# PiKVM_USB_Adapter_v1.net
KiCad netlist of a schematic drawn in EAGLE
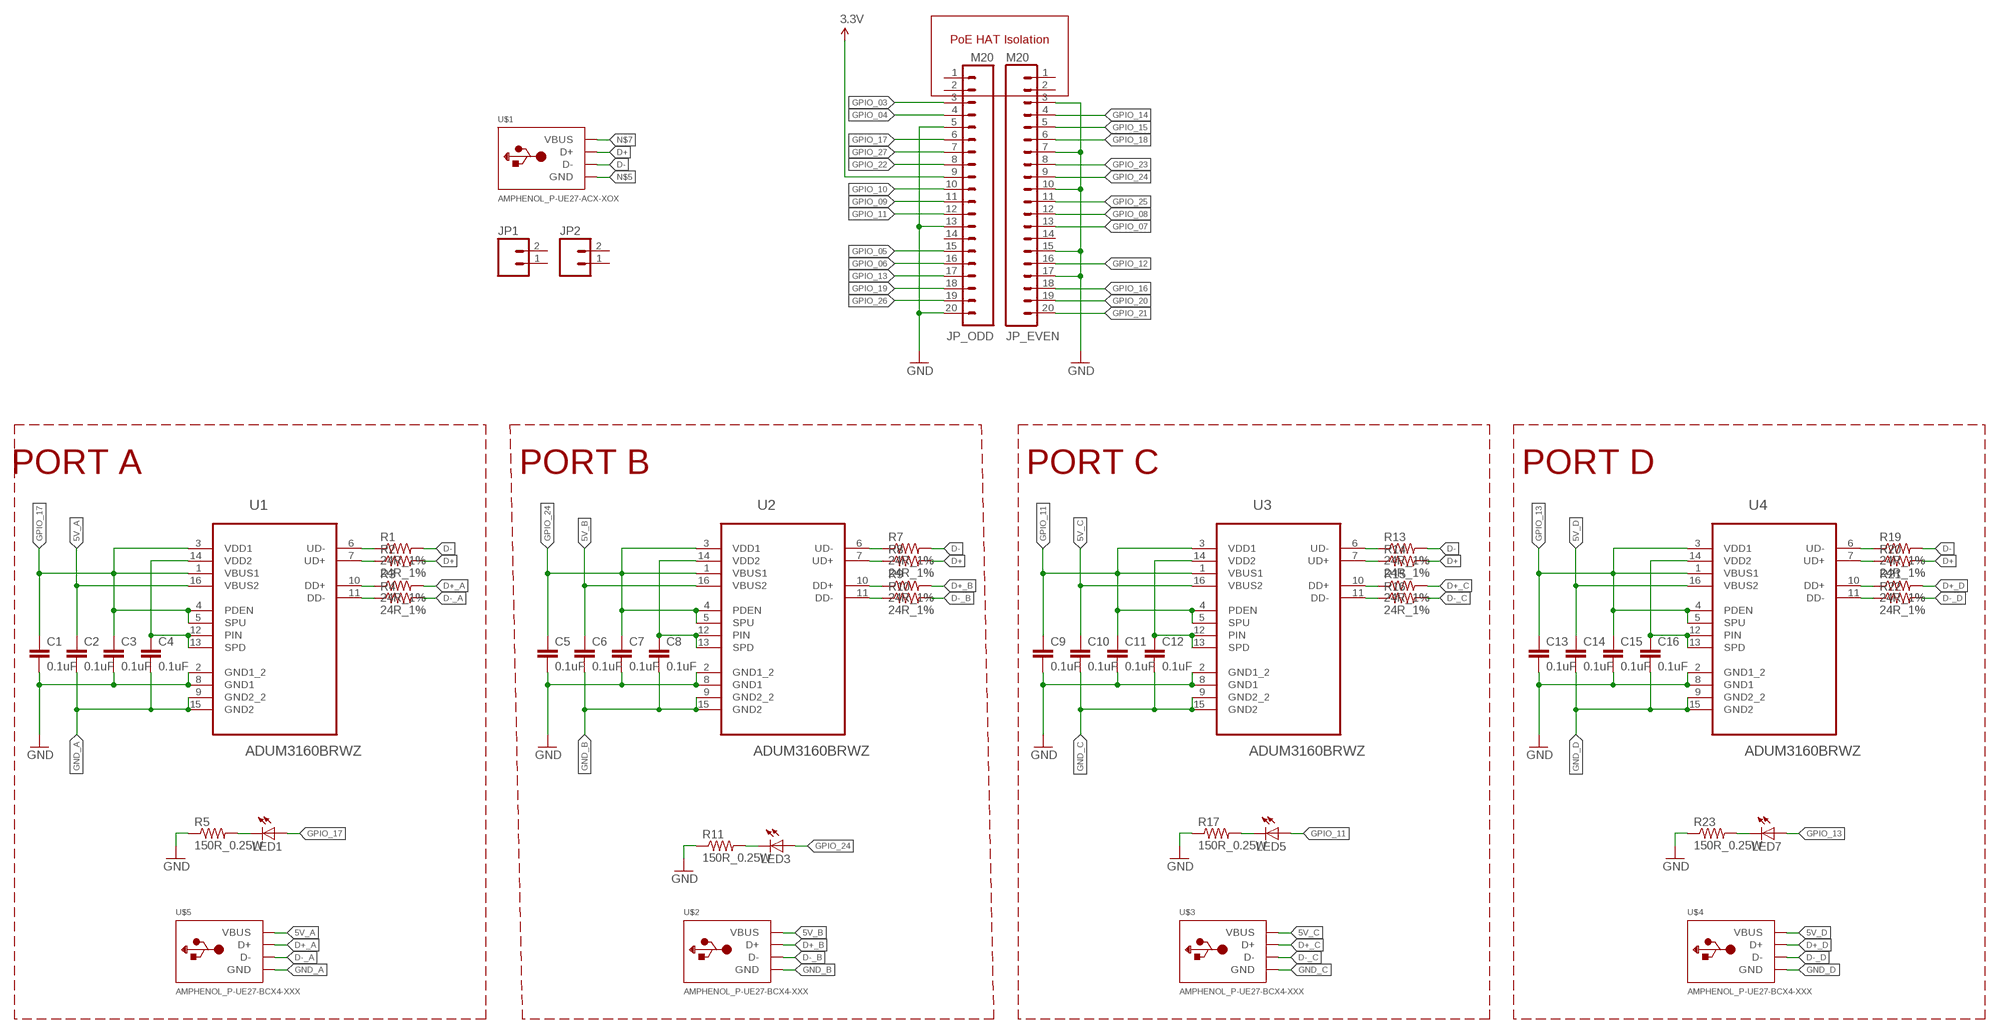
[diagram p0: schematic, sheet 1]

(export (version "E")
  (design (tool "Eeschema 10.0.6"))
  (components
    (comp (ref "C1")
      (value "0.1uF")
      (footprint "eagle-import:0805")
      (libsource (lib "eagle-import") (part "CAP0805"))
    )
    (comp (ref "C2")
      (value "0.1uF")
      (footprint "eagle-import:0805")
      (libsource (lib "eagle-import") (part "CAP0805"))
    )
    (comp (ref "C3")
      (value "0.1uF")
      (footprint "eagle-import:0805")
      (libsource (lib "eagle-import") (part "CAP0805"))
    )
    (comp (ref "C4")
      (value "0.1uF")
      (footprint "eagle-import:0805")
      (libsource (lib "eagle-import") (part "CAP0805"))
    )
    (comp (ref "C5")
      (value "0.1uF")
      (footprint "eagle-import:0805")
      (libsource (lib "eagle-import") (part "CAP0805"))
    )
    (comp (ref "C6")
      (value "0.1uF")
      (footprint "eagle-import:0805")
      (libsource (lib "eagle-import") (part "CAP0805"))
    )
    (comp (ref "C7")
      (value "0.1uF")
      (footprint "eagle-import:0805")
      (libsource (lib "eagle-import") (part "CAP0805"))
    )
    (comp (ref "C8")
      (value "0.1uF")
      (footprint "eagle-import:0805")
      (libsource (lib "eagle-import") (part "CAP0805"))
    )
    (comp (ref "C9")
      (value "0.1uF")
      (footprint "eagle-import:0805")
      (libsource (lib "eagle-import") (part "CAP0805"))
    )
    (comp (ref "C10")
      (value "0.1uF")
      (footprint "eagle-import:0805")
      (libsource (lib "eagle-import") (part "CAP0805"))
    )
    (comp (ref "C11")
      (value "0.1uF")
      (footprint "eagle-import:0805")
      (libsource (lib "eagle-import") (part "CAP0805"))
    )
    (comp (ref "C12")
      (value "0.1uF")
      (footprint "eagle-import:0805")
      (libsource (lib "eagle-import") (part "CAP0805"))
    )
    (comp (ref "C13")
      (value "0.1uF")
      (footprint "eagle-import:0805")
      (libsource (lib "eagle-import") (part "CAP0805"))
    )
    (comp (ref "C14")
      (value "0.1uF")
      (footprint "eagle-import:0805")
      (libsource (lib "eagle-import") (part "CAP0805"))
    )
    (comp (ref "C15")
      (value "0.1uF")
      (footprint "eagle-import:0805")
      (libsource (lib "eagle-import") (part "CAP0805"))
    )
    (comp (ref "C16")
      (value "0.1uF")
      (footprint "eagle-import:0805")
      (libsource (lib "eagle-import") (part "CAP0805"))
    )
    (comp (ref "JP1")
      (value "M02LOCK")
      (footprint "eagle-import:1X02_LOCK")
      (libsource (lib "eagle-import") (part "M02LOCK"))
    )
    (comp (ref "JP2")
      (value "M02LOCK")
      (footprint "eagle-import:1X02_LOCK")
      (libsource (lib "eagle-import") (part "M02LOCK"))
    )
    (comp (ref "JP_EVEN")
      (value "M20")
      (footprint "eagle-import:1X20")
      (libsource (lib "eagle-import") (part "M20"))
    )
    (comp (ref "JP_ODD")
      (value "M20")
      (footprint "eagle-import:1X20")
      (libsource (lib "eagle-import") (part "M20"))
    )
    (comp (ref "LED1")
      (value "LED1206")
      (footprint "eagle-import:LED-1206")
      (libsource (lib "eagle-import") (part "LED1206"))
    )
    (comp (ref "LED3")
      (value "LED1206")
      (footprint "eagle-import:LED-1206")
      (libsource (lib "eagle-import") (part "LED1206"))
    )
    (comp (ref "LED5")
      (value "LED1206")
      (footprint "eagle-import:LED-1206")
      (libsource (lib "eagle-import") (part "LED1206"))
    )
    (comp (ref "LED7")
      (value "LED1206")
      (footprint "eagle-import:LED-1206")
      (libsource (lib "eagle-import") (part "LED1206"))
    )
    (comp (ref "R1")
      (value "24R_1%")
      (footprint "eagle-import:0805")
      (libsource (lib "eagle-import") (part "RESISTOR0805-RES"))
    )
    (comp (ref "R2")
      (value "24R_1%")
      (footprint "eagle-import:0805")
      (libsource (lib "eagle-import") (part "RESISTOR0805-RES"))
    )
    (comp (ref "R3")
      (value "24R_1%")
      (footprint "eagle-import:0805")
      (libsource (lib "eagle-import") (part "RESISTOR0805-RES"))
    )
    (comp (ref "R4")
      (value "24R_1%")
      (footprint "eagle-import:0805")
      (libsource (lib "eagle-import") (part "RESISTOR0805-RES"))
    )
    (comp (ref "R5")
      (value "150R_0.25W")
      (footprint "eagle-import:1206")
      (libsource (lib "eagle-import") (part "RESISTOR1206"))
    )
    (comp (ref "R7")
      (value "24R_1%")
      (footprint "eagle-import:0805")
      (libsource (lib "eagle-import") (part "RESISTOR0805-RES"))
    )
    (comp (ref "R8")
      (value "24R_1%")
      (footprint "eagle-import:0805")
      (libsource (lib "eagle-import") (part "RESISTOR0805-RES"))
    )
    (comp (ref "R9")
      (value "24R_1%")
      (footprint "eagle-import:0805")
      (libsource (lib "eagle-import") (part "RESISTOR0805-RES"))
    )
    (comp (ref "R10")
      (value "24R_1%")
      (footprint "eagle-import:0805")
      (libsource (lib "eagle-import") (part "RESISTOR0805-RES"))
    )
    (comp (ref "R11")
      (value "150R_0.25W")
      (footprint "eagle-import:1206")
      (libsource (lib "eagle-import") (part "RESISTOR1206"))
    )
    (comp (ref "R13")
      (value "24R_1%")
      (footprint "eagle-import:0805")
      (libsource (lib "eagle-import") (part "RESISTOR0805-RES"))
    )
    (comp (ref "R14")
      (value "24R_1%")
      (footprint "eagle-import:0805")
      (libsource (lib "eagle-import") (part "RESISTOR0805-RES"))
    )
    (comp (ref "R15")
      (value "24R_1%")
      (footprint "eagle-import:0805")
      (libsource (lib "eagle-import") (part "RESISTOR0805-RES"))
    )
    (comp (ref "R16")
      (value "24R_1%")
      (footprint "eagle-import:0805")
      (libsource (lib "eagle-import") (part "RESISTOR0805-RES"))
    )
    (comp (ref "R17")
      (value "150R_0.25W")
      (footprint "eagle-import:1206")
      (libsource (lib "eagle-import") (part "RESISTOR1206"))
    )
    (comp (ref "R19")
      (value "24R_1%")
      (footprint "eagle-import:0805")
      (libsource (lib "eagle-import") (part "RESISTOR0805-RES"))
    )
    (comp (ref "R20")
      (value "24R_1%")
      (footprint "eagle-import:0805")
      (libsource (lib "eagle-import") (part "RESISTOR0805-RES"))
    )
    (comp (ref "R21")
      (value "24R_1%")
      (footprint "eagle-import:0805")
      (libsource (lib "eagle-import") (part "RESISTOR0805-RES"))
    )
    (comp (ref "R22")
      (value "24R_1%")
      (footprint "eagle-import:0805")
      (libsource (lib "eagle-import") (part "RESISTOR0805-RES"))
    )
    (comp (ref "R23")
      (value "150R_0.25W")
      (footprint "eagle-import:1206")
      (libsource (lib "eagle-import") (part "RESISTOR1206"))
    )
    (comp (ref "U$1")
      (value "AMPHENOL_P-UE27-ACX-XOX")
      (footprint "eagle-import:USBA_AMPHENOL-UE27-RA")
      (libsource (lib "eagle-import") (part "AMPHENOL_P-UE27-ACX-XOX"))
    )
    (comp (ref "U$2")
      (value "AMPHENOL_P-UE27-BCX4-XXX")
      (footprint "eagle-import:USBB_AMPHENOL-UE27-BC")
      (libsource (lib "eagle-import") (part "AMPHENOL_P-UE27-BCX4-XXX"))
    )
    (comp (ref "U$3")
      (value "AMPHENOL_P-UE27-BCX4-XXX")
      (footprint "eagle-import:USBB_AMPHENOL-UE27-BC")
      (libsource (lib "eagle-import") (part "AMPHENOL_P-UE27-BCX4-XXX"))
    )
    (comp (ref "U$4")
      (value "AMPHENOL_P-UE27-BCX4-XXX")
      (footprint "eagle-import:USBB_AMPHENOL-UE27-BC")
      (libsource (lib "eagle-import") (part "AMPHENOL_P-UE27-BCX4-XXX"))
    )
    (comp (ref "U$5")
      (value "AMPHENOL_P-UE27-BCX4-XXX")
      (footprint "eagle-import:USBB_AMPHENOL-UE27-BC")
      (libsource (lib "eagle-import") (part "AMPHENOL_P-UE27-BCX4-XXX"))
    )
    (comp (ref "U1")
      (value "ADUM3160BRWZ")
      (footprint "eagle-import:SOIC127P1032X265-16N")
      (libsource (lib "eagle-import") (part "ADUM3160BRWZ"))
    )
    (comp (ref "U2")
      (value "ADUM3160BRWZ")
      (footprint "eagle-import:SOIC127P1032X265-16N")
      (libsource (lib "eagle-import") (part "ADUM3160BRWZ"))
    )
    (comp (ref "U3")
      (value "ADUM3160BRWZ")
      (footprint "eagle-import:SOIC127P1032X265-16N")
      (libsource (lib "eagle-import") (part "ADUM3160BRWZ"))
    )
    (comp (ref "U4")
      (value "ADUM3160BRWZ")
      (footprint "eagle-import:SOIC127P1032X265-16N")
      (libsource (lib "eagle-import") (part "ADUM3160BRWZ"))
    )
  )
  (nets
    (net (code "1") (name "3.3V") (class "Default")
      (node (ref "JP_ODD") (pin "9") (pinfunction "9_9") (pintype "passive"))
    )
    (net (code "2") (name "5V_A") (class "Default")
      (node (ref "C2") (pin "1") (pinfunction "1_1") (pintype "passive"))
      (node (ref "U$5") (pin "P$1") (pinfunction "VBUS_P$1") (pintype "power_in"))
      (node (ref "U1") (pin "16") (pinfunction "VBUS2_16") (pintype "power_in"))
    )
    (net (code "3") (name "5V_B") (class "Default")
      (node (ref "C6") (pin "1") (pinfunction "1_1") (pintype "passive"))
      (node (ref "U$2") (pin "P$1") (pinfunction "VBUS_P$1") (pintype "power_in"))
      (node (ref "U2") (pin "16") (pinfunction "VBUS2_16") (pintype "power_in"))
    )
    (net (code "4") (name "5V_C") (class "Default")
      (node (ref "C10") (pin "1") (pinfunction "1_1") (pintype "passive"))
      (node (ref "U$3") (pin "P$1") (pinfunction "VBUS_P$1") (pintype "power_in"))
      (node (ref "U3") (pin "16") (pinfunction "VBUS2_16") (pintype "power_in"))
    )
    (net (code "5") (name "5V_D") (class "Default")
      (node (ref "C14") (pin "1") (pinfunction "1_1") (pintype "passive"))
      (node (ref "U$4") (pin "P$1") (pinfunction "VBUS_P$1") (pintype "power_in"))
      (node (ref "U4") (pin "16") (pinfunction "VBUS2_16") (pintype "power_in"))
    )
    (net (code "6") (name "D+") (class "Default")
      (node (ref "R14") (pin "2") (pinfunction "2_2") (pintype "passive"))
      (node (ref "R2") (pin "2") (pinfunction "2_2") (pintype "passive"))
      (node (ref "R20") (pin "2") (pinfunction "2_2") (pintype "passive"))
      (node (ref "R8") (pin "2") (pinfunction "2_2") (pintype "passive"))
      (node (ref "U$1") (pin "P$3") (pinfunction "D+_P$3") (pintype "bidirectional"))
    )
    (net (code "7") (name "D+_A") (class "Default")
      (node (ref "R3") (pin "2") (pinfunction "2_2") (pintype "passive"))
      (node (ref "U$5") (pin "P$3") (pinfunction "D+_P$3") (pintype "bidirectional"))
    )
    (net (code "8") (name "D+_B") (class "Default")
      (node (ref "R9") (pin "2") (pinfunction "2_2") (pintype "passive"))
      (node (ref "U$2") (pin "P$3") (pinfunction "D+_P$3") (pintype "bidirectional"))
    )
    (net (code "9") (name "D+_C") (class "Default")
      (node (ref "R15") (pin "2") (pinfunction "2_2") (pintype "passive"))
      (node (ref "U$3") (pin "P$3") (pinfunction "D+_P$3") (pintype "bidirectional"))
    )
    (net (code "10") (name "D+_D") (class "Default")
      (node (ref "R21") (pin "2") (pinfunction "2_2") (pintype "passive"))
      (node (ref "U$4") (pin "P$3") (pinfunction "D+_P$3") (pintype "bidirectional"))
    )
    (net (code "11") (name "D-") (class "Default")
      (node (ref "R1") (pin "2") (pinfunction "2_2") (pintype "passive"))
      (node (ref "R13") (pin "2") (pinfunction "2_2") (pintype "passive"))
      (node (ref "R19") (pin "2") (pinfunction "2_2") (pintype "passive"))
      (node (ref "R7") (pin "2") (pinfunction "2_2") (pintype "passive"))
      (node (ref "U$1") (pin "P$2") (pinfunction "D-_P$2") (pintype "bidirectional"))
    )
    (net (code "12") (name "D-_A") (class "Default")
      (node (ref "R4") (pin "2") (pinfunction "2_2") (pintype "passive"))
      (node (ref "U$5") (pin "P$2") (pinfunction "D-_P$2") (pintype "bidirectional"))
    )
    (net (code "13") (name "D-_B") (class "Default")
      (node (ref "R10") (pin "2") (pinfunction "2_2") (pintype "passive"))
      (node (ref "U$2") (pin "P$2") (pinfunction "D-_P$2") (pintype "bidirectional"))
    )
    (net (code "14") (name "D-_C") (class "Default")
      (node (ref "R16") (pin "2") (pinfunction "2_2") (pintype "passive"))
      (node (ref "U$3") (pin "P$2") (pinfunction "D-_P$2") (pintype "bidirectional"))
    )
    (net (code "15") (name "D-_D") (class "Default")
      (node (ref "R22") (pin "2") (pinfunction "2_2") (pintype "passive"))
      (node (ref "U$4") (pin "P$2") (pinfunction "D-_P$2") (pintype "bidirectional"))
    )
    (net (code "16") (name "GND") (class "Default")
      (node (ref "C1") (pin "2") (pinfunction "2_2") (pintype "passive"))
      (node (ref "C11") (pin "2") (pinfunction "2_2") (pintype "passive"))
      (node (ref "C13") (pin "2") (pinfunction "2_2") (pintype "passive"))
      (node (ref "C15") (pin "2") (pinfunction "2_2") (pintype "passive"))
      (node (ref "C3") (pin "2") (pinfunction "2_2") (pintype "passive"))
      (node (ref "C5") (pin "2") (pinfunction "2_2") (pintype "passive"))
      (node (ref "C7") (pin "2") (pinfunction "2_2") (pintype "passive"))
      (node (ref "C9") (pin "2") (pinfunction "2_2") (pintype "passive"))
      (node (ref "JP_EVEN") (pin "10") (pinfunction "10_10") (pintype "passive"))
      (node (ref "JP_EVEN") (pin "15") (pinfunction "15_15") (pintype "passive"))
      (node (ref "JP_EVEN") (pin "17") (pinfunction "17_17") (pintype "passive"))
      (node (ref "JP_EVEN") (pin "3") (pinfunction "3_3") (pintype "passive"))
      (node (ref "JP_EVEN") (pin "7") (pinfunction "7_7") (pintype "passive"))
      (node (ref "JP_ODD") (pin "13") (pinfunction "13_13") (pintype "passive"))
      (node (ref "JP_ODD") (pin "20") (pinfunction "20_20") (pintype "passive"))
      (node (ref "JP_ODD") (pin "5") (pinfunction "5_5") (pintype "passive"))
      (node (ref "R11") (pin "1") (pinfunction "1_1") (pintype "passive"))
      (node (ref "R17") (pin "1") (pinfunction "1_1") (pintype "passive"))
      (node (ref "R23") (pin "1") (pinfunction "1_1") (pintype "passive"))
      (node (ref "R5") (pin "1") (pinfunction "1_1") (pintype "passive"))
      (node (ref "U1") (pin "2") (pinfunction "GND1_2_2") (pintype "passive"))
      (node (ref "U1") (pin "8") (pinfunction "GND1_8") (pintype "passive"))
      (node (ref "U2") (pin "2") (pinfunction "GND1_2_2") (pintype "passive"))
      (node (ref "U2") (pin "8") (pinfunction "GND1_8") (pintype "passive"))
      (node (ref "U3") (pin "2") (pinfunction "GND1_2_2") (pintype "passive"))
      (node (ref "U3") (pin "8") (pinfunction "GND1_8") (pintype "passive"))
      (node (ref "U4") (pin "2") (pinfunction "GND1_2_2") (pintype "passive"))
      (node (ref "U4") (pin "8") (pinfunction "GND1_8") (pintype "passive"))
    )
    (net (code "17") (name "GND_A") (class "Default")
      (node (ref "C2") (pin "2") (pinfunction "2_2") (pintype "passive"))
      (node (ref "C4") (pin "2") (pinfunction "2_2") (pintype "passive"))
      (node (ref "U$5") (pin "P$4") (pinfunction "GND_P$4") (pintype "power_in"))
      (node (ref "U1") (pin "15") (pinfunction "GND2_15") (pintype "passive"))
      (node (ref "U1") (pin "9") (pinfunction "GND2_2_9") (pintype "passive"))
    )
    (net (code "18") (name "GND_B") (class "Default")
      (node (ref "C6") (pin "2") (pinfunction "2_2") (pintype "passive"))
      (node (ref "C8") (pin "2") (pinfunction "2_2") (pintype "passive"))
      (node (ref "U$2") (pin "P$4") (pinfunction "GND_P$4") (pintype "power_in"))
      (node (ref "U2") (pin "15") (pinfunction "GND2_15") (pintype "passive"))
      (node (ref "U2") (pin "9") (pinfunction "GND2_2_9") (pintype "passive"))
    )
    (net (code "19") (name "GND_C") (class "Default")
      (node (ref "C10") (pin "2") (pinfunction "2_2") (pintype "passive"))
      (node (ref "C12") (pin "2") (pinfunction "2_2") (pintype "passive"))
      (node (ref "U$3") (pin "P$4") (pinfunction "GND_P$4") (pintype "power_in"))
      (node (ref "U3") (pin "15") (pinfunction "GND2_15") (pintype "passive"))
      (node (ref "U3") (pin "9") (pinfunction "GND2_2_9") (pintype "passive"))
    )
    (net (code "20") (name "GND_D") (class "Default")
      (node (ref "C14") (pin "2") (pinfunction "2_2") (pintype "passive"))
      (node (ref "C16") (pin "2") (pinfunction "2_2") (pintype "passive"))
      (node (ref "U$4") (pin "P$4") (pinfunction "GND_P$4") (pintype "power_in"))
      (node (ref "U4") (pin "15") (pinfunction "GND2_15") (pintype "passive"))
      (node (ref "U4") (pin "9") (pinfunction "GND2_2_9") (pintype "passive"))
    )
    (net (code "21") (name "GPIO_03") (class "Default")
      (node (ref "JP_ODD") (pin "3") (pinfunction "3_3") (pintype "passive"))
    )
    (net (code "22") (name "GPIO_04") (class "Default")
      (node (ref "JP_ODD") (pin "4") (pinfunction "4_4") (pintype "passive"))
    )
    (net (code "23") (name "GPIO_05") (class "Default")
      (node (ref "JP_ODD") (pin "15") (pinfunction "15_15") (pintype "passive"))
    )
    (net (code "24") (name "GPIO_06") (class "Default")
      (node (ref "JP_ODD") (pin "16") (pinfunction "16_16") (pintype "passive"))
    )
    (net (code "25") (name "GPIO_07") (class "Default")
      (node (ref "JP_EVEN") (pin "13") (pinfunction "13_13") (pintype "passive"))
    )
    (net (code "26") (name "GPIO_08") (class "Default")
      (node (ref "JP_EVEN") (pin "12") (pinfunction "12_12") (pintype "passive"))
    )
    (net (code "27") (name "GPIO_09") (class "Default")
      (node (ref "JP_ODD") (pin "11") (pinfunction "11_11") (pintype "passive"))
    )
    (net (code "28") (name "GPIO_10") (class "Default")
      (node (ref "JP_ODD") (pin "10") (pinfunction "10_10") (pintype "passive"))
    )
    (net (code "29") (name "GPIO_11") (class "Default")
      (node (ref "C11") (pin "1") (pinfunction "1_1") (pintype "passive"))
      (node (ref "C9") (pin "1") (pinfunction "1_1") (pintype "passive"))
      (node (ref "JP_ODD") (pin "12") (pinfunction "12_12") (pintype "passive"))
      (node (ref "LED5") (pin "A") (pinfunction "A_A") (pintype "passive"))
      (node (ref "U3") (pin "1") (pinfunction "VBUS1_1") (pintype "power_in"))
      (node (ref "U3") (pin "3") (pinfunction "VDD1_3") (pintype "power_in"))
      (node (ref "U3") (pin "4") (pinfunction "PDEN_4") (pintype "input"))
      (node (ref "U3") (pin "5") (pinfunction "SPU_5") (pintype "input"))
    )
    (net (code "30") (name "GPIO_12") (class "Default")
      (node (ref "JP_EVEN") (pin "16") (pinfunction "16_16") (pintype "passive"))
    )
    (net (code "31") (name "GPIO_13") (class "Default")
      (node (ref "C13") (pin "1") (pinfunction "1_1") (pintype "passive"))
      (node (ref "C15") (pin "1") (pinfunction "1_1") (pintype "passive"))
      (node (ref "JP_ODD") (pin "17") (pinfunction "17_17") (pintype "passive"))
      (node (ref "LED7") (pin "A") (pinfunction "A_A") (pintype "passive"))
      (node (ref "U4") (pin "1") (pinfunction "VBUS1_1") (pintype "power_in"))
      (node (ref "U4") (pin "3") (pinfunction "VDD1_3") (pintype "power_in"))
      (node (ref "U4") (pin "4") (pinfunction "PDEN_4") (pintype "input"))
      (node (ref "U4") (pin "5") (pinfunction "SPU_5") (pintype "input"))
    )
    (net (code "32") (name "GPIO_14") (class "Default")
      (node (ref "JP_EVEN") (pin "4") (pinfunction "4_4") (pintype "passive"))
    )
    (net (code "33") (name "GPIO_15") (class "Default")
      (node (ref "JP_EVEN") (pin "5") (pinfunction "5_5") (pintype "passive"))
    )
    (net (code "34") (name "GPIO_16") (class "Default")
      (node (ref "JP_EVEN") (pin "18") (pinfunction "18_18") (pintype "passive"))
    )
    (net (code "35") (name "GPIO_17") (class "Default")
      (node (ref "C1") (pin "1") (pinfunction "1_1") (pintype "passive"))
      (node (ref "C3") (pin "1") (pinfunction "1_1") (pintype "passive"))
      (node (ref "JP_ODD") (pin "6") (pinfunction "6_6") (pintype "passive"))
      (node (ref "LED1") (pin "A") (pinfunction "A_A") (pintype "passive"))
      (node (ref "U1") (pin "1") (pinfunction "VBUS1_1") (pintype "power_in"))
      (node (ref "U1") (pin "3") (pinfunction "VDD1_3") (pintype "power_in"))
      (node (ref "U1") (pin "4") (pinfunction "PDEN_4") (pintype "input"))
      (node (ref "U1") (pin "5") (pinfunction "SPU_5") (pintype "input"))
    )
    (net (code "36") (name "GPIO_18") (class "Default")
      (node (ref "JP_EVEN") (pin "6") (pinfunction "6_6") (pintype "passive"))
    )
    (net (code "37") (name "GPIO_19") (class "Default")
      (node (ref "JP_ODD") (pin "18") (pinfunction "18_18") (pintype "passive"))
    )
    (net (code "38") (name "GPIO_20") (class "Default")
      (node (ref "JP_EVEN") (pin "19") (pinfunction "19_19") (pintype "passive"))
    )
    (net (code "39") (name "GPIO_21") (class "Default")
      (node (ref "JP_EVEN") (pin "20") (pinfunction "20_20") (pintype "passive"))
    )
    (net (code "40") (name "GPIO_22") (class "Default")
      (node (ref "JP_ODD") (pin "8") (pinfunction "8_8") (pintype "passive"))
    )
    (net (code "41") (name "GPIO_23") (class "Default")
      (node (ref "JP_EVEN") (pin "8") (pinfunction "8_8") (pintype "passive"))
    )
    (net (code "42") (name "GPIO_24") (class "Default")
      (node (ref "C5") (pin "1") (pinfunction "1_1") (pintype "passive"))
      (node (ref "C7") (pin "1") (pinfunction "1_1") (pintype "passive"))
      (node (ref "JP_EVEN") (pin "9") (pinfunction "9_9") (pintype "passive"))
      (node (ref "LED3") (pin "A") (pinfunction "A_A") (pintype "passive"))
      (node (ref "U2") (pin "1") (pinfunction "VBUS1_1") (pintype "power_in"))
      (node (ref "U2") (pin "3") (pinfunction "VDD1_3") (pintype "power_in"))
      (node (ref "U2") (pin "4") (pinfunction "PDEN_4") (pintype "input"))
      (node (ref "U2") (pin "5") (pinfunction "SPU_5") (pintype "input"))
    )
    (net (code "43") (name "GPIO_25") (class "Default")
      (node (ref "JP_EVEN") (pin "11") (pinfunction "11_11") (pintype "passive"))
    )
    (net (code "44") (name "GPIO_26") (class "Default")
      (node (ref "JP_ODD") (pin "19") (pinfunction "19_19") (pintype "passive"))
    )
    (net (code "45") (name "GPIO_27") (class "Default")
      (node (ref "JP_ODD") (pin "7") (pinfunction "7_7") (pintype "passive"))
    )
    (net (code "46") (name "N$5") (class "Default")
      (node (ref "U$1") (pin "P$4") (pinfunction "GND_P$4") (pintype "power_in"))
    )
    (net (code "47") (name "N$7") (class "Default")
      (node (ref "U$1") (pin "P$1") (pinfunction "VBUS_P$1") (pintype "power_in"))
    )
    (net (code "48") (name "Net-(LED1-PadC)") (class "Default")
      (node (ref "LED1") (pin "C") (pinfunction "C_C") (pintype "passive"))
      (node (ref "R5") (pin "2") (pinfunction "2_2") (pintype "passive"))
    )
    (net (code "49") (name "Net-(LED3-PadC)") (class "Default")
      (node (ref "LED3") (pin "C") (pinfunction "C_C") (pintype "passive"))
      (node (ref "R11") (pin "2") (pinfunction "2_2") (pintype "passive"))
    )
    (net (code "50") (name "Net-(LED5-PadC)") (class "Default")
      (node (ref "LED5") (pin "C") (pinfunction "C_C") (pintype "passive"))
      (node (ref "R17") (pin "2") (pinfunction "2_2") (pintype "passive"))
    )
    (net (code "51") (name "Net-(LED7-PadC)") (class "Default")
      (node (ref "LED7") (pin "C") (pinfunction "C_C") (pintype "passive"))
      (node (ref "R23") (pin "2") (pinfunction "2_2") (pintype "passive"))
    )
    (net (code "52") (name "Net-(U1-DD+)") (class "Default")
      (node (ref "R3") (pin "1") (pinfunction "1_1") (pintype "passive"))
      (node (ref "U1") (pin "10") (pinfunction "DD+_10") (pintype "bidirectional"))
    )
    (net (code "53") (name "Net-(U1-DD-)") (class "Default")
      (node (ref "R4") (pin "1") (pinfunction "1_1") (pintype "passive"))
      (node (ref "U1") (pin "11") (pinfunction "DD-_11") (pintype "bidirectional"))
    )
    (net (code "54") (name "Net-(U1-PIN)") (class "Default")
      (node (ref "C4") (pin "1") (pinfunction "1_1") (pintype "passive"))
      (node (ref "U1") (pin "12") (pinfunction "PIN_12") (pintype "input"))
      (node (ref "U1") (pin "13") (pinfunction "SPD_13") (pintype "input"))
      (node (ref "U1") (pin "14") (pinfunction "VDD2_14") (pintype "power_in"))
    )
    (net (code "55") (name "Net-(U1-UD+)") (class "Default")
      (node (ref "R2") (pin "1") (pinfunction "1_1") (pintype "passive"))
      (node (ref "U1") (pin "7") (pinfunction "UD+_7") (pintype "bidirectional"))
    )
    (net (code "56") (name "Net-(U1-UD-)") (class "Default")
      (node (ref "R1") (pin "1") (pinfunction "1_1") (pintype "passive"))
      (node (ref "U1") (pin "6") (pinfunction "UD-_6") (pintype "bidirectional"))
    )
    (net (code "57") (name "Net-(U2-DD+)") (class "Default")
      (node (ref "R9") (pin "1") (pinfunction "1_1") (pintype "passive"))
      (node (ref "U2") (pin "10") (pinfunction "DD+_10") (pintype "bidirectional"))
    )
    (net (code "58") (name "Net-(U2-DD-)") (class "Default")
      (node (ref "R10") (pin "1") (pinfunction "1_1") (pintype "passive"))
      (node (ref "U2") (pin "11") (pinfunction "DD-_11") (pintype "bidirectional"))
    )
    (net (code "59") (name "Net-(U2-PIN)") (class "Default")
      (node (ref "C8") (pin "1") (pinfunction "1_1") (pintype "passive"))
      (node (ref "U2") (pin "12") (pinfunction "PIN_12") (pintype "input"))
      (node (ref "U2") (pin "13") (pinfunction "SPD_13") (pintype "input"))
      (node (ref "U2") (pin "14") (pinfunction "VDD2_14") (pintype "power_in"))
    )
    (net (code "60") (name "Net-(U2-UD+)") (class "Default")
      (node (ref "R8") (pin "1") (pinfunction "1_1") (pintype "passive"))
      (node (ref "U2") (pin "7") (pinfunction "UD+_7") (pintype "bidirectional"))
    )
    (net (code "61") (name "Net-(U2-UD-)") (class "Default")
      (node (ref "R7") (pin "1") (pinfunction "1_1") (pintype "passive"))
      (node (ref "U2") (pin "6") (pinfunction "UD-_6") (pintype "bidirectional"))
    )
    (net (code "62") (name "Net-(U3-DD+)") (class "Default")
      (node (ref "R15") (pin "1") (pinfunction "1_1") (pintype "passive"))
      (node (ref "U3") (pin "10") (pinfunction "DD+_10") (pintype "bidirectional"))
    )
    (net (code "63") (name "Net-(U3-DD-)") (class "Default")
      (node (ref "R16") (pin "1") (pinfunction "1_1") (pintype "passive"))
      (node (ref "U3") (pin "11") (pinfunction "DD-_11") (pintype "bidirectional"))
    )
    (net (code "64") (name "Net-(U3-PIN)") (class "Default")
      (node (ref "C12") (pin "1") (pinfunction "1_1") (pintype "passive"))
      (node (ref "U3") (pin "12") (pinfunction "PIN_12") (pintype "input"))
      (node (ref "U3") (pin "13") (pinfunction "SPD_13") (pintype "input"))
      (node (ref "U3") (pin "14") (pinfunction "VDD2_14") (pintype "power_in"))
    )
    (net (code "65") (name "Net-(U3-UD+)") (class "Default")
      (node (ref "R14") (pin "1") (pinfunction "1_1") (pintype "passive"))
      (node (ref "U3") (pin "7") (pinfunction "UD+_7") (pintype "bidirectional"))
    )
    (net (code "66") (name "Net-(U3-UD-)") (class "Default")
      (node (ref "R13") (pin "1") (pinfunction "1_1") (pintype "passive"))
      (node (ref "U3") (pin "6") (pinfunction "UD-_6") (pintype "bidirectional"))
    )
    (net (code "67") (name "Net-(U4-DD+)") (class "Default")
      (node (ref "R21") (pin "1") (pinfunction "1_1") (pintype "passive"))
      (node (ref "U4") (pin "10") (pinfunction "DD+_10") (pintype "bidirectional"))
    )
    (net (code "68") (name "Net-(U4-DD-)") (class "Default")
      (node (ref "R22") (pin "1") (pinfunction "1_1") (pintype "passive"))
      (node (ref "U4") (pin "11") (pinfunction "DD-_11") (pintype "bidirectional"))
    )
    (net (code "69") (name "Net-(U4-PIN)") (class "Default")
      (node (ref "C16") (pin "1") (pinfunction "1_1") (pintype "passive"))
      (node (ref "U4") (pin "12") (pinfunction "PIN_12") (pintype "input"))
      (node (ref "U4") (pin "13") (pinfunction "SPD_13") (pintype "input"))
      (node (ref "U4") (pin "14") (pinfunction "VDD2_14") (pintype "power_in"))
    )
    (net (code "70") (name "Net-(U4-UD+)") (class "Default")
      (node (ref "R20") (pin "1") (pinfunction "1_1") (pintype "passive"))
      (node (ref "U4") (pin "7") (pinfunction "UD+_7") (pintype "bidirectional"))
    )
    (net (code "71") (name "Net-(U4-UD-)") (class "Default")
      (node (ref "R19") (pin "1") (pinfunction "1_1") (pintype "passive"))
      (node (ref "U4") (pin "6") (pinfunction "UD-_6") (pintype "bidirectional"))
    )
    (net (code "72") (name "unconnected-(JP1-Pad1)") (class "Default")
      (node (ref "JP1") (pin "1") (pinfunction "1_1") (pintype "passive"))
    )
    (net (code "73") (name "unconnected-(JP1-Pad2)") (class "Default")
      (node (ref "JP1") (pin "2") (pinfunction "2_2") (pintype "passive"))
    )
    (net (code "74") (name "unconnected-(JP2-Pad1)") (class "Default")
      (node (ref "JP2") (pin "1") (pinfunction "1_1") (pintype "passive"))
    )
    (net (code "75") (name "unconnected-(JP2-Pad2)") (class "Default")
      (node (ref "JP2") (pin "2") (pinfunction "2_2") (pintype "passive"))
    )
    (net (code "76") (name "unconnected-(JP_EVEN-Pad1)") (class "Default")
      (node (ref "JP_EVEN") (pin "1") (pinfunction "1_1") (pintype "passive"))
    )
    (net (code "77") (name "unconnected-(JP_EVEN-Pad2)") (class "Default")
      (node (ref "JP_EVEN") (pin "2") (pinfunction "2_2") (pintype "passive"))
    )
    (net (code "78") (name "unconnected-(JP_EVEN-Pad14)") (class "Default")
      (node (ref "JP_EVEN") (pin "14") (pinfunction "14_14") (pintype "passive"))
    )
    (net (code "79") (name "unconnected-(JP_ODD-Pad1)") (class "Default")
      (node (ref "JP_ODD") (pin "1") (pinfunction "1_1") (pintype "passive"))
    )
    (net (code "80") (name "unconnected-(JP_ODD-Pad2)") (class "Default")
      (node (ref "JP_ODD") (pin "2") (pinfunction "2_2") (pintype "passive"))
    )
    (net (code "81") (name "unconnected-(JP_ODD-Pad14)") (class "Default")
      (node (ref "JP_ODD") (pin "14") (pinfunction "14_14") (pintype "passive"))
    )
  )
)
